# Status.net
KiCad netlist of a schematic drawn in Altium Designer
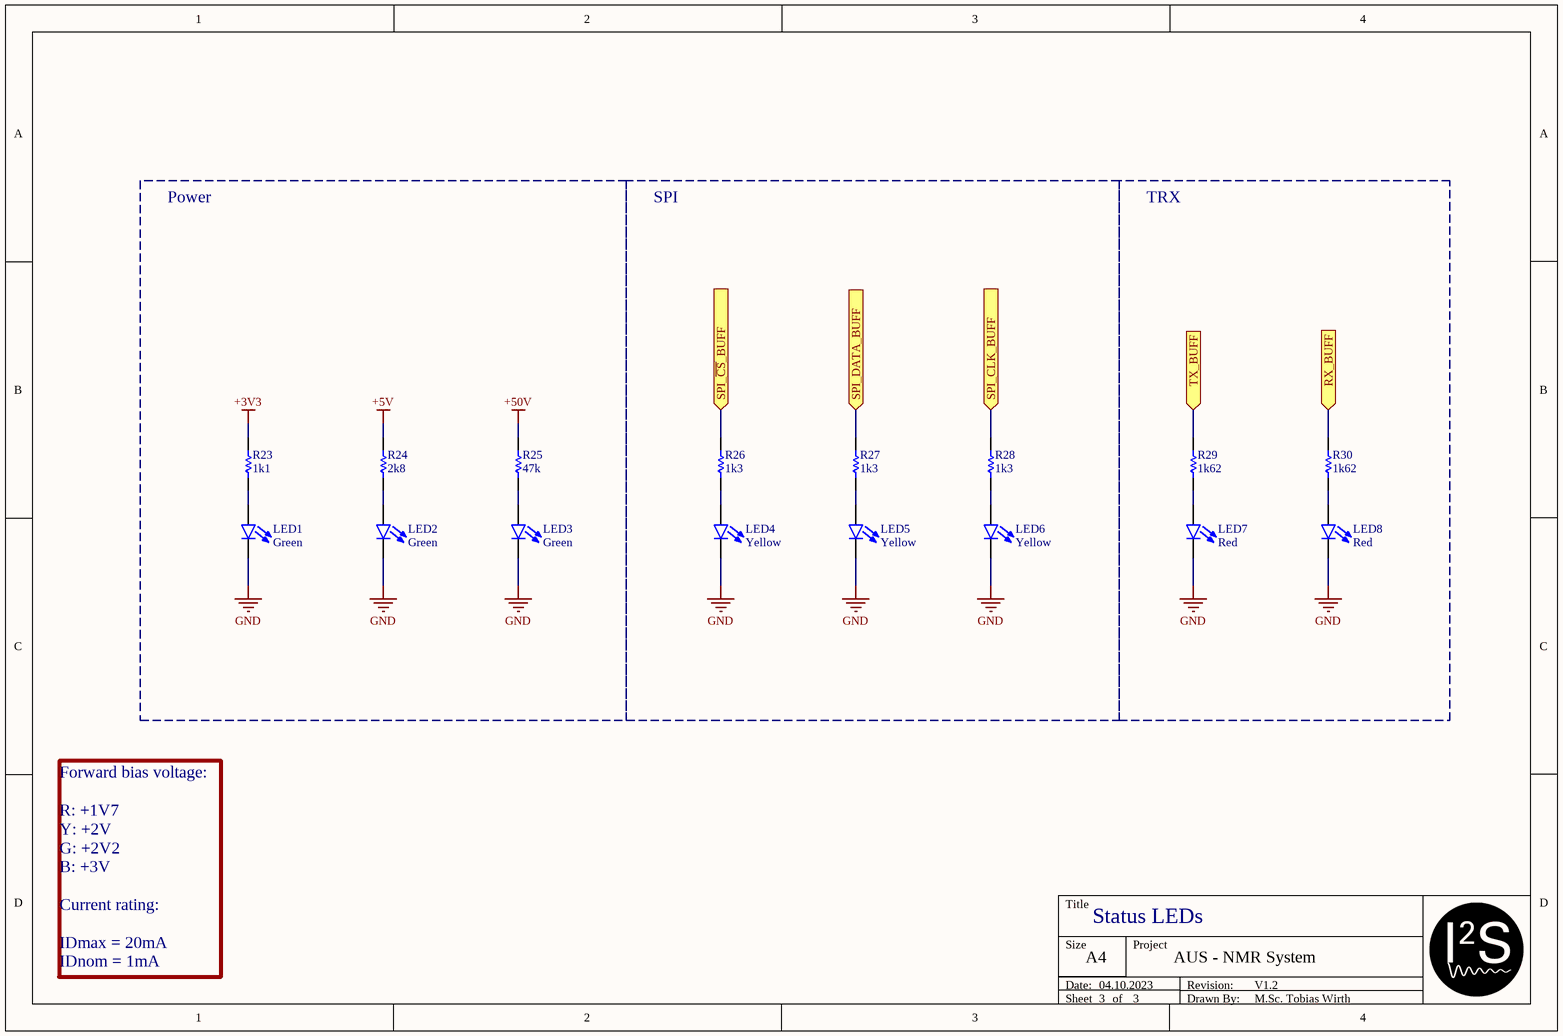
[diagram p0: Status.SchDoc]

(export (version "E")
  (design (tool "Eeschema 10.0.6"))
  (components
    (comp (ref "LED1") (value "Green") (footprint "RES_0603") (libsource (lib "IIS-Lib_TW") (part "LED")))
    (comp (ref "LED2") (value "Green") (footprint "RES_0603") (libsource (lib "IIS-Lib_TW") (part "LED")))
    (comp (ref "LED3") (value "Green") (footprint "RES_0603") (libsource (lib "IIS-Lib_TW") (part "LED")))
    (comp (ref "LED4") (value "Yellow") (footprint "RES_0603") (libsource (lib "IIS-Lib_TW") (part "LED")))
    (comp (ref "LED5") (value "Yellow") (footprint "RES_0603") (libsource (lib "IIS-Lib_TW") (part "LED")))
    (comp (ref "LED6") (value "Yellow") (footprint "RES_0603") (libsource (lib "IIS-Lib_TW") (part "LED")))
    (comp (ref "LED7") (value "Red") (footprint "RES_0603") (libsource (lib "IIS-Lib_TW") (part "LED")))
    (comp (ref "LED8") (value "Red") (footprint "RES_0603") (libsource (lib "IIS-Lib_TW") (part "LED")))
    (comp (ref "R23") (value "1k1") (footprint "RES_0402") (libsource (lib "IIS-Lib_TW") (part "Res")))
    (comp (ref "R24") (value "2k8") (footprint "RES_0402") (libsource (lib "IIS-Lib_TW") (part "Res")))
    (comp (ref "R25") (value "47k") (footprint "RES_0402") (libsource (lib "IIS-Lib_TW") (part "Res")))
    (comp (ref "R26") (value "1k3") (footprint "RES_0402") (libsource (lib "IIS-Lib_TW") (part "Res")))
    (comp (ref "R27") (value "1k3") (footprint "RES_0402") (libsource (lib "IIS-Lib_TW") (part "Res")))
    (comp (ref "R28") (value "1k3") (footprint "RES_0402") (libsource (lib "IIS-Lib_TW") (part "Res")))
    (comp (ref "R29") (value "1k62") (footprint "RES_0402") (libsource (lib "IIS-Lib_TW") (part "Res")))
    (comp (ref "R30") (value "1k62") (footprint "RES_0402") (libsource (lib "IIS-Lib_TW") (part "Res")))
  )
  (nets
    (net (code "1") (name "+3V3") (class "Default")
      (node (ref "R23") (pin "2") (pinfunction "2_2") (pintype "passive"))
    )
    (net (code "2") (name "+5V") (class "Default")
      (node (ref "R24") (pin "2") (pinfunction "2_2") (pintype "passive"))
    )
    (net (code "3") (name "+50V") (class "Default")
      (node (ref "R25") (pin "2") (pinfunction "2_2") (pintype "passive"))
    )
    (net (code "4") (name "/RX_BUFF") (class "Default")
      (node (ref "R30") (pin "2") (pinfunction "2_2") (pintype "passive"))
    )
    (net (code "5") (name "/SPI_CLK_BUFF") (class "Default")
      (node (ref "R28") (pin "2") (pinfunction "2_2") (pintype "passive"))
    )
    (net (code "6") (name "/SPI_DATA_BUFF") (class "Default")
      (node (ref "R27") (pin "2") (pinfunction "2_2") (pintype "passive"))
    )
    (net (code "7") (name "/SPI_~{CS}_BUFF") (class "Default")
      (node (ref "R26") (pin "2") (pinfunction "2_2") (pintype "passive"))
    )
    (net (code "8") (name "/TX_BUFF") (class "Default")
      (node (ref "R29") (pin "2") (pinfunction "2_2") (pintype "passive"))
    )
    (net (code "9") (name "GND") (class "Default")
      (node (ref "LED1") (pin "2") (pinfunction "2_2") (pintype "passive"))
      (node (ref "LED2") (pin "2") (pinfunction "2_2") (pintype "passive"))
      (node (ref "LED3") (pin "2") (pinfunction "2_2") (pintype "passive"))
      (node (ref "LED4") (pin "2") (pinfunction "2_2") (pintype "passive"))
      (node (ref "LED5") (pin "2") (pinfunction "2_2") (pintype "passive"))
      (node (ref "LED6") (pin "2") (pinfunction "2_2") (pintype "passive"))
      (node (ref "LED7") (pin "2") (pinfunction "2_2") (pintype "passive"))
      (node (ref "LED8") (pin "2") (pinfunction "2_2") (pintype "passive"))
    )
    (net (code "10") (name "Net-(LED1-Pad1)") (class "Default")
      (node (ref "LED1") (pin "1") (pinfunction "1_1") (pintype "passive"))
      (node (ref "R23") (pin "1") (pinfunction "1_1") (pintype "passive"))
    )
    (net (code "11") (name "Net-(LED2-Pad1)") (class "Default")
      (node (ref "LED2") (pin "1") (pinfunction "1_1") (pintype "passive"))
      (node (ref "R24") (pin "1") (pinfunction "1_1") (pintype "passive"))
    )
    (net (code "12") (name "Net-(LED3-Pad1)") (class "Default")
      (node (ref "LED3") (pin "1") (pinfunction "1_1") (pintype "passive"))
      (node (ref "R25") (pin "1") (pinfunction "1_1") (pintype "passive"))
    )
    (net (code "13") (name "Net-(LED4-Pad1)") (class "Default")
      (node (ref "LED4") (pin "1") (pinfunction "1_1") (pintype "passive"))
      (node (ref "R26") (pin "1") (pinfunction "1_1") (pintype "passive"))
    )
    (net (code "14") (name "Net-(LED5-Pad1)") (class "Default")
      (node (ref "LED5") (pin "1") (pinfunction "1_1") (pintype "passive"))
      (node (ref "R27") (pin "1") (pinfunction "1_1") (pintype "passive"))
    )
    (net (code "15") (name "Net-(LED6-Pad1)") (class "Default")
      (node (ref "LED6") (pin "1") (pinfunction "1_1") (pintype "passive"))
      (node (ref "R28") (pin "1") (pinfunction "1_1") (pintype "passive"))
    )
    (net (code "16") (name "Net-(LED7-Pad1)") (class "Default")
      (node (ref "LED7") (pin "1") (pinfunction "1_1") (pintype "passive"))
      (node (ref "R29") (pin "1") (pinfunction "1_1") (pintype "passive"))
    )
    (net (code "17") (name "Net-(LED8-Pad1)") (class "Default")
      (node (ref "LED8") (pin "1") (pinfunction "1_1") (pintype "passive"))
      (node (ref "R30") (pin "1") (pinfunction "1_1") (pintype "passive"))
    )
  )
)
